# main.net
KiCad netlist of a schematic drawn in Altium Designer
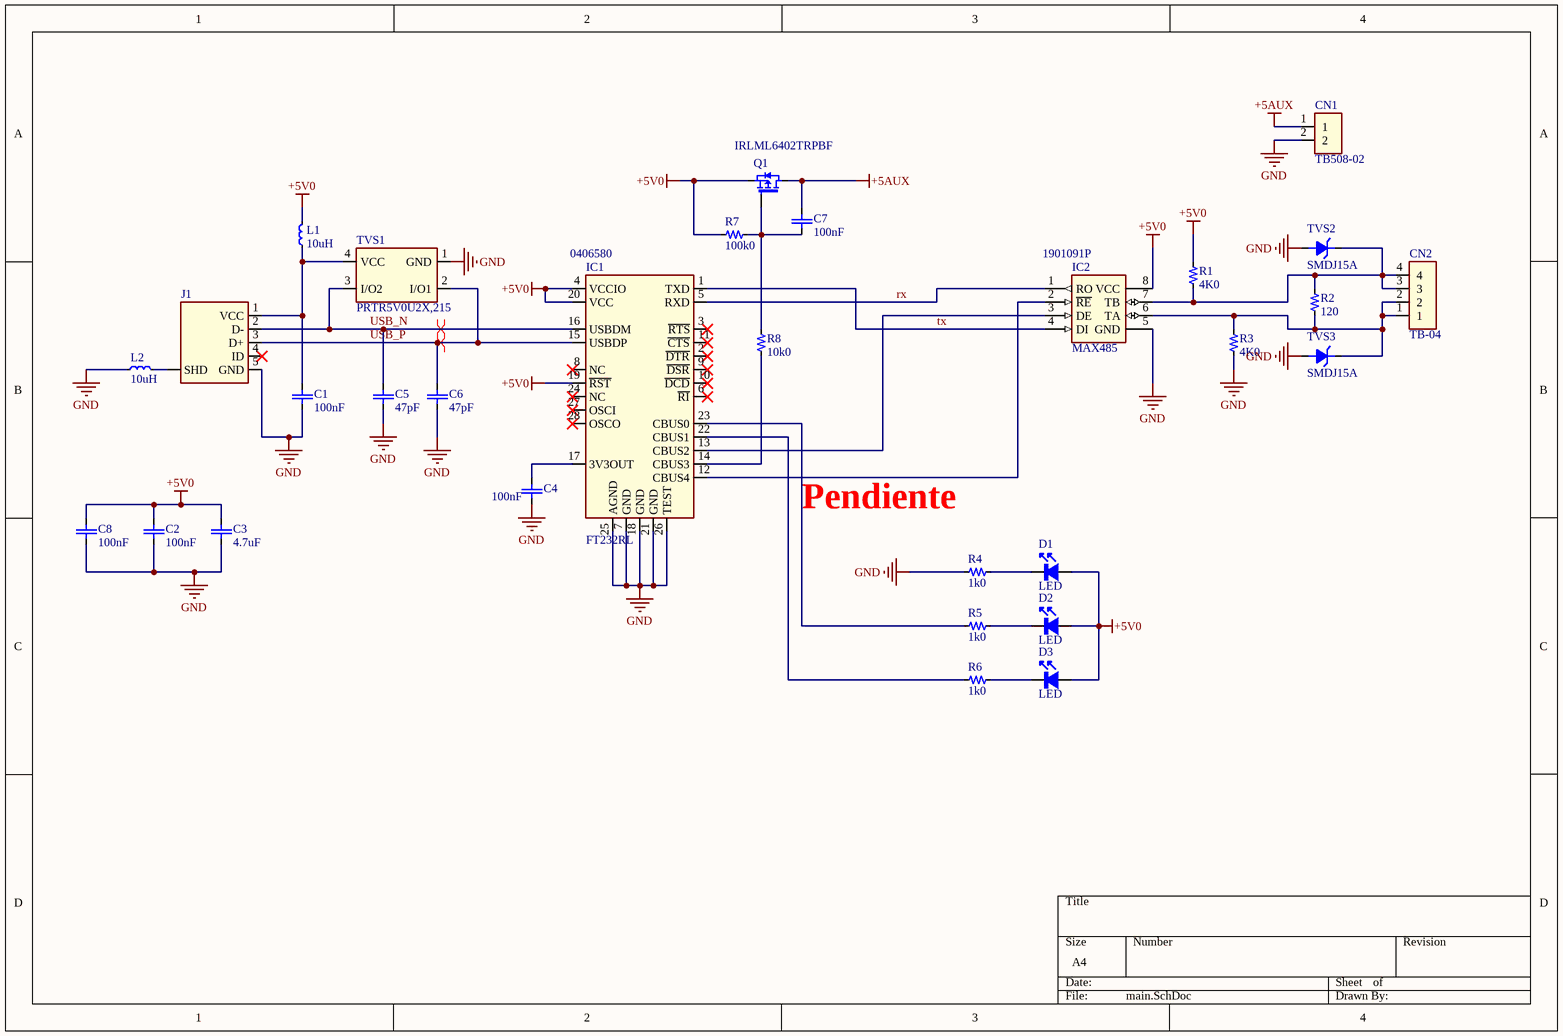
[diagram p0: main.SchDoc]

(export (version "E")
  (design (tool "Eeschema 10.0.6"))
  (components
    (comp (ref "C1")
      (value "100nF")
      (footprint "C0805")
      (description "Capacitor without polarity")
      (fields (field (name "VOLTAGE") "25V"))
      (libsource (lib "RasUNMSM") (part "Capacitor"))
    )
    (comp (ref "C2")
      (value "100nF")
      (footprint "C0805")
      (description "Capacitor without polarity")
      (fields (field (name "VOLTAGE") "25V"))
      (libsource (lib "RasUNMSM") (part "Capacitor"))
    )
    (comp (ref "C3")
      (value "4.7uF")
      (footprint "C0805")
      (description "Capacitor without polarity")
      (fields (field (name "VOLTAGE") "25V"))
      (libsource (lib "") (part "Capacitor_1"))
    )
    (comp (ref "C4")
      (value "100nF")
      (footprint "C0805")
      (description "Capacitor without polarity")
      (fields (field (name "VOLTAGE") "25V"))
      (libsource (lib "RasUNMSM") (part "Capacitor"))
    )
    (comp (ref "C5")
      (value "47pF")
      (footprint "C0805")
      (description "Capacitor without polarity")
      (fields (field (name "VOLTAGE") "25V"))
      (libsource (lib "RasUNMSM") (part "Capacitor"))
    )
    (comp (ref "C6")
      (value "47pF")
      (footprint "C0805")
      (description "Capacitor without polarity")
      (fields (field (name "VOLTAGE") "25V"))
      (libsource (lib "RasUNMSM") (part "Capacitor"))
    )
    (comp (ref "C7")
      (value "100nF")
      (footprint "C0805")
      (description "Capacitor without polarity")
      (fields (field (name "VOLTAGE") "25V"))
      (libsource (lib "RasUNMSM") (part "Capacitor"))
    )
    (comp (ref "C8")
      (value "100nF")
      (footprint "C0805")
      (description "Capacitor without polarity")
      (fields (field (name "VOLTAGE") "25V"))
      (libsource (lib "RasUNMSM") (part "Capacitor"))
    )
    (comp (ref "CN1")
      (value "TB508-02")
      (footprint "TB508-02")
      (description "Terminal Block")
      (libsource (lib "RasUNMSM") (part "TB-02"))
    )
    (comp (ref "CN2")
      (value "TB-04")
      (footprint "TB508-04")
      (description "Terminal Block")
      (libsource (lib "RasUNMSM") (part "TB-04"))
    )
    (comp (ref "D1")
      (value "LED")
      (footprint "LED-1210")
      (description "LED - Light-Emitting Diode")
      (libsource (lib "RasUNMSM") (part "LED"))
    )
    (comp (ref "D2")
      (value "LED")
      (footprint "LED-0805")
      (description "LED - Light-Emitting Diode")
      (libsource (lib "RasUNMSM") (part "LED"))
    )
    (comp (ref "D3")
      (value "LED")
      (footprint "LED-0805")
      (description "LED - Light-Emitting Diode")
      (libsource (lib "RasUNMSM") (part "LED"))
    )
    (comp (ref "IC1")
      (value "FT232RL")
      (footprint "SSOP-28")
      (description "USB Bridge, USB to UART USB 2.0 UART Interface 28-SSOP")
      (fields (field (name "SUPPLIER PART NUMBER 1") "0406580"))
      (libsource (lib "RasUNMSM") (part "FT232"))
    )
    (comp (ref "IC2")
      (value "MAX485")
      (footprint "SOIC8-N")
      (description "IC TRANSCEIVER HALF 1/1 8SOIC")
      (fields (field (name "SUPPLIER PART NUMBER 1") "1901091P"))
      (libsource (lib "RasUNMSM") (part "MAX485"))
    )
    (comp (ref "J1")
      (value "690-005-299-043")
      (footprint "USB-Mini")
      (description "CONN RCPT USB2.0 MINI B SMD R/A")
      (libsource (lib "RasUNMSM") (part "USB-Mini-B"))
    )
    (comp (ref "L1")
      (value "10uH")
      (footprint "L0805")
      (description "Inductor for low power")
      (libsource (lib "RasUNMSM") (part "Inductor"))
    )
    (comp (ref "L2")
      (value "10uH")
      (footprint "L0805")
      (description "Inductor for low power")
      (libsource (lib "RasUNMSM") (part "Inductor"))
    )
    (comp (ref "Q1")
      (value "IRLML6402TRPBF")
      (footprint "SOT23-3")
      (description "P-Channel 20V 3.7A (Ta) 1.3W (Ta) /SOT-23 - LowPower")
      (libsource (lib "RasUNMSM") (part "MOSFET-P-LP"))
    )
    (comp (ref "R1")
      (value "4K0")
      (footprint "R0805")
      (description "Single resistor")
      (fields (field (name "POWER") "0.125W"))
      (libsource (lib "RasUNMSM") (part "Resistor"))
    )
    (comp (ref "R2")
      (value "120")
      (footprint "R0805")
      (description "Single resistor")
      (fields (field (name "POWER") "0.125W"))
      (libsource (lib "RasUNMSM") (part "Resistor"))
    )
    (comp (ref "R3")
      (value "4K0")
      (footprint "R0805")
      (description "Single resistor")
      (fields (field (name "POWER") "0.125W"))
      (libsource (lib "RasUNMSM") (part "Resistor"))
    )
    (comp (ref "R4")
      (value "1k0")
      (footprint "R0805")
      (description "Single resistor")
      (fields (field (name "POWER") "0.125W"))
      (libsource (lib "RasUNMSM") (part "Resistor"))
    )
    (comp (ref "R5")
      (value "1k0")
      (footprint "R0805")
      (description "Single resistor")
      (fields (field (name "POWER") "0.125W"))
      (libsource (lib "RasUNMSM") (part "Resistor"))
    )
    (comp (ref "R6")
      (value "1k0")
      (footprint "R0805")
      (description "Single resistor")
      (fields (field (name "POWER") "0.125W"))
      (libsource (lib "RasUNMSM") (part "Resistor"))
    )
    (comp (ref "R7")
      (value "100k0")
      (footprint "R0805")
      (description "Single resistor")
      (fields (field (name "POWER") "0.125W"))
      (libsource (lib "RasUNMSM") (part "Resistor"))
    )
    (comp (ref "R8")
      (value "10k0")
      (footprint "R0805")
      (description "Single resistor")
      (fields (field (name "POWER") "0.125W"))
      (libsource (lib "RasUNMSM") (part "Resistor"))
    )
    (comp (ref "TVS1")
      (value "PRTR5V0U2X,215")
      (footprint "SOT143-4")
      (description "Clamp  Ipp Tvs Diode Surface Mount SOT-143B")
      (libsource (lib "RasUNMSM") (part "TVS-DUAL-SOT143B"))
    )
    (comp (ref "TVS2")
      (value "SMDJ15A")
      (footprint "SOD123")
      (description "TVS DIODE - Transient Voltage Suppression Diode")
      (libsource (lib "RasUNMSM") (part "TVS-SINGLE"))
    )
    (comp (ref "TVS3")
      (value "SMDJ15A")
      (footprint "SOD123")
      (description "TVS DIODE - Transient Voltage Suppression Diode")
      (libsource (lib "RasUNMSM") (part "TVS-SINGLE"))
    )
  )
  (nets
    (net (code "1") (name "+5AUX") (class "Default")
      (node (ref "C7") (pin "2") (pinfunction "2_2") (pintype "passive"))
      (node (ref "CN1") (pin "1") (pinfunction "1_1") (pintype "passive"))
      (node (ref "Q1") (pin "3") (pinfunction "D_3") (pintype "passive"))
    )
    (net (code "2") (name "+5V0") (class "Default")
      (node (ref "C2") (pin "2") (pinfunction "2_2") (pintype "passive"))
      (node (ref "C3") (pin "1") (pinfunction "1_1") (pintype "passive"))
      (node (ref "C8") (pin "2") (pinfunction "2_2") (pintype "passive"))
      (node (ref "D1") (pin "2") (pinfunction "2_2") (pintype "passive"))
      (node (ref "D2") (pin "2") (pinfunction "2_2") (pintype "passive"))
      (node (ref "D3") (pin "2") (pinfunction "2_2") (pintype "passive"))
      (node (ref "IC1") (pin "19") (pinfunction "~{RST}_19") (pintype "passive"))
      (node (ref "IC1") (pin "20") (pinfunction "VCC_20") (pintype "passive"))
      (node (ref "IC1") (pin "4") (pinfunction "VCCIO_4") (pintype "passive"))
      (node (ref "IC2") (pin "8") (pinfunction "VCC_8") (pintype "power_in"))
      (node (ref "L1") (pin "2") (pinfunction "2_2") (pintype "passive"))
      (node (ref "Q1") (pin "2") (pinfunction "S_2") (pintype "passive"))
      (node (ref "R1") (pin "2") (pinfunction "2_2") (pintype "passive"))
      (node (ref "R7") (pin "1") (pinfunction "1_1") (pintype "passive"))
    )
    (net (code "3") (name "/USB_N") (class "Default")
      (node (ref "C5") (pin "2") (pinfunction "2_2") (pintype "passive"))
      (node (ref "IC1") (pin "16") (pinfunction "USBDM_16") (pintype "passive"))
      (node (ref "J1") (pin "2") (pinfunction "D-_2") (pintype "passive"))
      (node (ref "TVS1") (pin "3") (pinfunction "I/O2_3") (pintype "passive"))
    )
    (net (code "4") (name "/USB_P") (class "Default")
      (node (ref "C6") (pin "2") (pinfunction "2_2") (pintype "passive"))
      (node (ref "IC1") (pin "15") (pinfunction "USBDP_15") (pintype "passive"))
      (node (ref "J1") (pin "3") (pinfunction "D+_3") (pintype "passive"))
      (node (ref "TVS1") (pin "2") (pinfunction "I/O1_2") (pintype "passive"))
    )
    (net (code "5") (name "/rx") (class "Default")
      (node (ref "IC1") (pin "5") (pinfunction "RXD_5") (pintype "passive"))
      (node (ref "IC2") (pin "1") (pinfunction "RO_1") (pintype "output"))
    )
    (net (code "6") (name "/tx") (class "Default")
      (node (ref "IC1") (pin "1") (pinfunction "TXD_1") (pintype "passive"))
      (node (ref "IC2") (pin "4") (pinfunction "DI_4") (pintype "input"))
    )
    (net (code "7") (name "GND") (class "Default")
      (node (ref "C1") (pin "1") (pinfunction "1_1") (pintype "passive"))
      (node (ref "C2") (pin "1") (pinfunction "1_1") (pintype "passive"))
      (node (ref "C3") (pin "2") (pinfunction "2_2") (pintype "passive"))
      (node (ref "C4") (pin "1") (pinfunction "1_1") (pintype "passive"))
      (node (ref "C5") (pin "1") (pinfunction "1_1") (pintype "passive"))
      (node (ref "C6") (pin "1") (pinfunction "1_1") (pintype "passive"))
      (node (ref "C8") (pin "1") (pinfunction "1_1") (pintype "passive"))
      (node (ref "CN1") (pin "2") (pinfunction "2_2") (pintype "passive"))
      (node (ref "IC1") (pin "18") (pinfunction "GND_18") (pintype "passive"))
      (node (ref "IC1") (pin "21") (pinfunction "GND_21") (pintype "passive"))
      (node (ref "IC1") (pin "25") (pinfunction "AGND_25") (pintype "passive"))
      (node (ref "IC1") (pin "26") (pinfunction "TEST_26") (pintype "passive"))
      (node (ref "IC1") (pin "7") (pinfunction "GND_7") (pintype "passive"))
      (node (ref "IC2") (pin "5") (pinfunction "GND_5") (pintype "power_in"))
      (node (ref "J1") (pin "5") (pinfunction "GND_5") (pintype "passive"))
      (node (ref "L2") (pin "1") (pinfunction "1_1") (pintype "passive"))
      (node (ref "R3") (pin "1") (pinfunction "1_1") (pintype "passive"))
      (node (ref "R4") (pin "1") (pinfunction "1_1") (pintype "passive"))
      (node (ref "TVS1") (pin "1") (pinfunction "GND_1") (pintype "passive"))
      (node (ref "TVS2") (pin "2") (pinfunction "2_2") (pintype "passive"))
      (node (ref "TVS3") (pin "2") (pinfunction "2_2") (pintype "passive"))
    )
    (net (code "8") (name "Net-(D1-Pad1)") (class "Default")
      (node (ref "D1") (pin "1") (pinfunction "1_1") (pintype "passive"))
      (node (ref "R4") (pin "2") (pinfunction "2_2") (pintype "passive"))
    )
    (net (code "9") (name "Net-(D2-Pad1)") (class "Default")
      (node (ref "D2") (pin "1") (pinfunction "1_1") (pintype "passive"))
      (node (ref "R5") (pin "2") (pinfunction "2_2") (pintype "passive"))
    )
    (net (code "10") (name "Net-(D3-Pad1)") (class "Default")
      (node (ref "D3") (pin "1") (pinfunction "1_1") (pintype "passive"))
      (node (ref "R6") (pin "2") (pinfunction "2_2") (pintype "passive"))
    )
    (net (code "11") (name "Net-(IC1-3V3OUT)") (class "Default")
      (node (ref "C4") (pin "2") (pinfunction "2_2") (pintype "passive"))
      (node (ref "IC1") (pin "17") (pinfunction "3V3OUT_17") (pintype "passive"))
    )
    (net (code "12") (name "Net-(IC1-CBUS0)") (class "Default")
      (node (ref "IC1") (pin "23") (pinfunction "CBUS0_23") (pintype "passive"))
      (node (ref "R5") (pin "1") (pinfunction "1_1") (pintype "passive"))
    )
    (net (code "13") (name "Net-(IC1-CBUS1)") (class "Default")
      (node (ref "IC1") (pin "22") (pinfunction "CBUS1_22") (pintype "passive"))
      (node (ref "R6") (pin "1") (pinfunction "1_1") (pintype "passive"))
    )
    (net (code "14") (name "Net-(IC1-CBUS2)") (class "Default")
      (node (ref "IC1") (pin "13") (pinfunction "CBUS2_13") (pintype "passive"))
      (node (ref "IC2") (pin "3") (pinfunction "DE_3") (pintype "input"))
    )
    (net (code "15") (name "Net-(IC1-CBUS3)") (class "Default")
      (node (ref "IC1") (pin "14") (pinfunction "CBUS3_14") (pintype "passive"))
      (node (ref "R8") (pin "1") (pinfunction "1_1") (pintype "passive"))
    )
    (net (code "16") (name "Net-(IC1-CBUS4)") (class "Default")
      (node (ref "IC1") (pin "12") (pinfunction "CBUS4_12") (pintype "passive"))
      (node (ref "IC2") (pin "2") (pinfunction "~{RE}_2") (pintype "input"))
    )
    (net (code "17") (name "Net-(IC2-TA)") (class "Default")
      (node (ref "CN2") (pin "1") (pinfunction "1_1") (pintype "passive"))
      (node (ref "CN2") (pin "2") (pinfunction "2_2") (pintype "passive"))
      (node (ref "IC2") (pin "6") (pinfunction "TA_6") (pintype "bidirectional"))
      (node (ref "R2") (pin "1") (pinfunction "1_1") (pintype "passive"))
      (node (ref "R3") (pin "2") (pinfunction "2_2") (pintype "passive"))
      (node (ref "TVS3") (pin "1") (pinfunction "1_1") (pintype "passive"))
    )
    (net (code "18") (name "Net-(IC2-TB)") (class "Default")
      (node (ref "CN2") (pin "3") (pinfunction "3_3") (pintype "passive"))
      (node (ref "CN2") (pin "4") (pinfunction "4_4") (pintype "passive"))
      (node (ref "IC2") (pin "7") (pinfunction "TB_7") (pintype "bidirectional"))
      (node (ref "R1") (pin "1") (pinfunction "1_1") (pintype "passive"))
      (node (ref "R2") (pin "2") (pinfunction "2_2") (pintype "passive"))
      (node (ref "TVS2") (pin "1") (pinfunction "1_1") (pintype "passive"))
    )
    (net (code "19") (name "Net-(J1-PadSHD)") (class "Default")
      (node (ref "J1") (pin "SHD") (pinfunction "SHD_SHD") (pintype "passive"))
      (node (ref "L2") (pin "2") (pinfunction "2_2") (pintype "passive"))
    )
    (net (code "20") (name "Net-(J1-VCC)") (class "Default")
      (node (ref "C1") (pin "2") (pinfunction "2_2") (pintype "passive"))
      (node (ref "J1") (pin "1") (pinfunction "VCC_1") (pintype "passive"))
      (node (ref "L1") (pin "1") (pinfunction "1_1") (pintype "passive"))
      (node (ref "TVS1") (pin "4") (pinfunction "VCC_4") (pintype "passive"))
    )
    (net (code "21") (name "Net-(Q1-G)") (class "Default")
      (node (ref "C7") (pin "1") (pinfunction "1_1") (pintype "passive"))
      (node (ref "Q1") (pin "1") (pinfunction "G_1") (pintype "passive"))
      (node (ref "R7") (pin "2") (pinfunction "2_2") (pintype "passive"))
      (node (ref "R8") (pin "2") (pinfunction "2_2") (pintype "passive"))
    )
    (net (code "22") (name "unconnected-(IC1-NC-Pad8)") (class "Default")
      (node (ref "IC1") (pin "8") (pinfunction "NC_8") (pintype "passive+no_connect"))
    )
    (net (code "23") (name "unconnected-(IC1-NC-Pad24)") (class "Default")
      (node (ref "IC1") (pin "24") (pinfunction "NC_24") (pintype "passive+no_connect"))
    )
    (net (code "24") (name "unconnected-(IC1-OSCI-Pad27)") (class "Default")
      (node (ref "IC1") (pin "27") (pinfunction "OSCI_27") (pintype "passive+no_connect"))
    )
    (net (code "25") (name "unconnected-(IC1-OSCO-Pad28)") (class "Default")
      (node (ref "IC1") (pin "28") (pinfunction "OSCO_28") (pintype "passive+no_connect"))
    )
    (net (code "26") (name "unconnected-(IC1-~{CTS}-Pad11)") (class "Default")
      (node (ref "IC1") (pin "11") (pinfunction "~{CTS}_11") (pintype "passive+no_connect"))
    )
    (net (code "27") (name "unconnected-(IC1-~{DCD}-Pad10)") (class "Default")
      (node (ref "IC1") (pin "10") (pinfunction "~{DCD}_10") (pintype "passive+no_connect"))
    )
    (net (code "28") (name "unconnected-(IC1-~{DSR}-Pad9)") (class "Default")
      (node (ref "IC1") (pin "9") (pinfunction "~{DSR}_9") (pintype "passive+no_connect"))
    )
    (net (code "29") (name "unconnected-(IC1-~{DTR}-Pad2)") (class "Default")
      (node (ref "IC1") (pin "2") (pinfunction "~{DTR}_2") (pintype "passive+no_connect"))
    )
    (net (code "30") (name "unconnected-(IC1-~{RI}-Pad6)") (class "Default")
      (node (ref "IC1") (pin "6") (pinfunction "~{RI}_6") (pintype "passive+no_connect"))
    )
    (net (code "31") (name "unconnected-(IC1-~{RTS}-Pad3)") (class "Default")
      (node (ref "IC1") (pin "3") (pinfunction "~{RTS}_3") (pintype "passive+no_connect"))
    )
    (net (code "32") (name "unconnected-(J1-ID-Pad4)") (class "Default")
      (node (ref "J1") (pin "4") (pinfunction "ID_4") (pintype "passive+no_connect"))
    )
  )
)
